# VL53L1X-TOF-Sensor.net
KiCad netlist of a schematic drawn in EAGLE
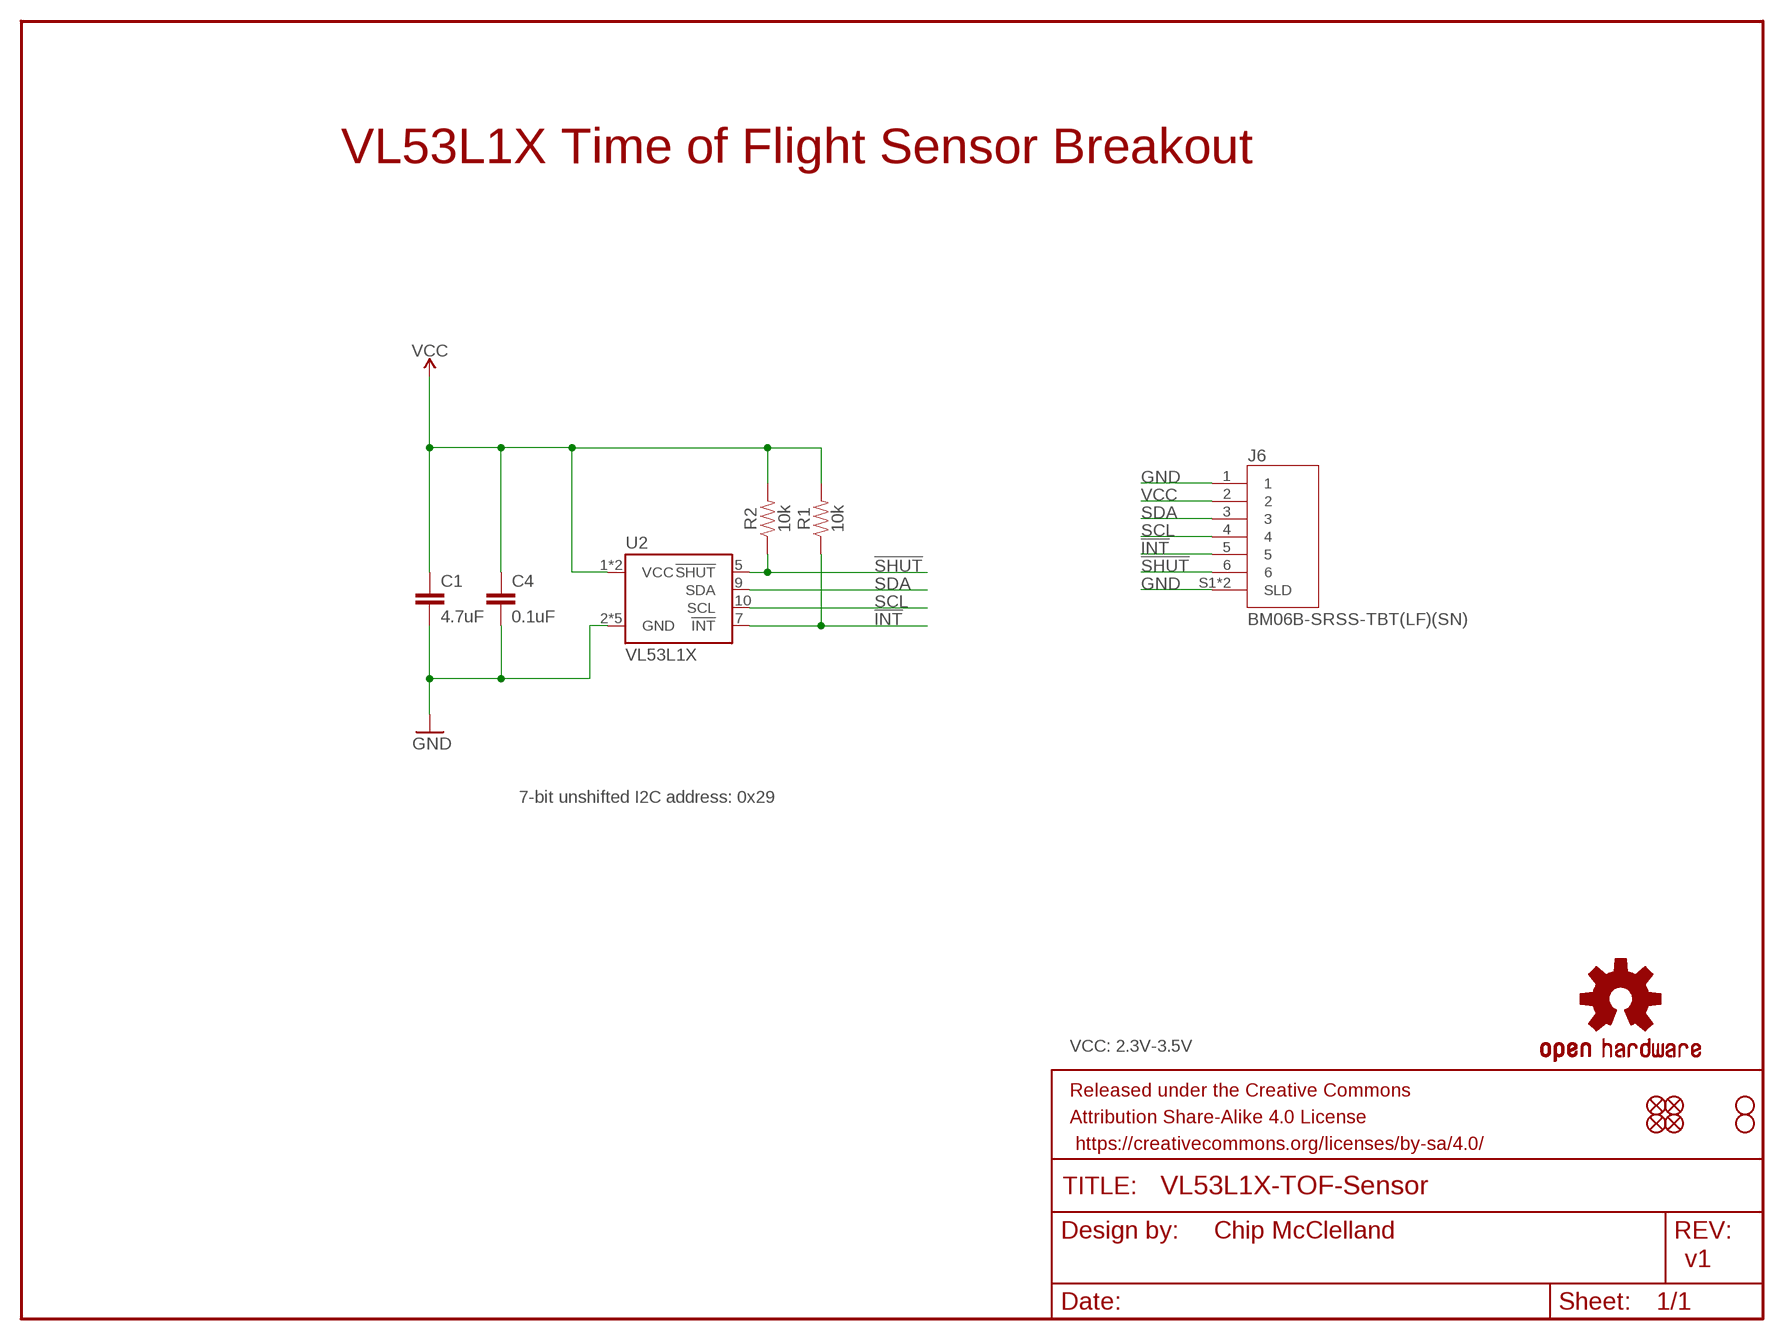
[diagram p0: schematic, sheet 1]

(export (version "E")
  (design (tool "Eeschema 10.0.6"))
  (components
    (comp (ref "C1")
      (value "4.7uF")
      (footprint "eagle-import:0603")
      (libsource (lib "eagle-import") (part "4.7UF0603"))
    )
    (comp (ref "C4")
      (value "0.1uF")
      (footprint "eagle-import:0603")
      (libsource (lib "eagle-import") (part "0.1UF-0603-25V-(+80/-20%)"))
    )
    (comp (ref "FRAME1")
      (value "FRAME-LETTER")
      (footprint "eagle-import:CREATIVE_COMMONS")
      (libsource (lib "eagle-import") (part "FRAME-LETTER"))
    )
    (comp (ref "J6")
      (value "BM06B-SRSS-TBT(LF)(SN)")
      (footprint "eagle-import:JST_BM06B-SRSS-TB(LF)(SN)")
      (libsource (lib "eagle-import") (part "BM06B-SRSS-TBT(LF)(SN)"))
    )
    (comp (ref "JP1")
      (value "FIDUCIALUFIDUCIAL")
      (footprint "eagle-import:MICRO-FIDUCIAL")
      (libsource (lib "eagle-import") (part "FIDUCIALUFIDUCIAL"))
    )
    (comp (ref "JP2")
      (value "FIDUCIALUFIDUCIAL")
      (footprint "eagle-import:MICRO-FIDUCIAL")
      (libsource (lib "eagle-import") (part "FIDUCIALUFIDUCIAL"))
    )
    (comp (ref "JP3")
      (value "STAND-OFF")
      (footprint "eagle-import:STAND-OFF")
      (libsource (lib "eagle-import") (part "STAND-OFF"))
    )
    (comp (ref "JP4")
      (value "STAND-OFF")
      (footprint "eagle-import:STAND-OFF")
      (libsource (lib "eagle-import") (part "STAND-OFF"))
    )
    (comp (ref "JP5")
      (value "FIDUCIALUFIDUCIAL")
      (footprint "eagle-import:MICRO-FIDUCIAL")
      (libsource (lib "eagle-import") (part "FIDUCIALUFIDUCIAL"))
    )
    (comp (ref "JP6")
      (value "FIDUCIALUFIDUCIAL")
      (footprint "eagle-import:MICRO-FIDUCIAL")
      (libsource (lib "eagle-import") (part "FIDUCIALUFIDUCIAL"))
    )
    (comp (ref "LOGO1")
      (value "OSHW-LOGOMINI")
      (footprint "eagle-import:OSHW-LOGO-MINI")
      (libsource (lib "eagle-import") (part "OSHW-LOGOMINI"))
    )
    (comp (ref "R1")
      (value "10k")
      (footprint "eagle-import:0603")
      (libsource (lib "eagle-import") (part "10KOHM-0603-1/10W-1%"))
    )
    (comp (ref "R2")
      (value "10k")
      (footprint "eagle-import:0603")
      (libsource (lib "eagle-import") (part "10KOHM-0603-1/10W-1%"))
    )
    (comp (ref "U2")
      (value "VL53L1X")
      (footprint "eagle-import:VL53L1X")
      (libsource (lib "eagle-import") (part "VL53L1XSMD"))
    )
  )
  (nets
    (net (code "1") (name "/SCL") (class "Default")
      (node (ref "J6") (pin "4") (pinfunction "4_4") (pintype "passive"))
      (node (ref "U2") (pin "10") (pinfunction "SCL_10") (pintype "bidirectional"))
    )
    (net (code "2") (name "/SDA") (class "Default")
      (node (ref "J6") (pin "3") (pinfunction "3_3") (pintype "passive"))
      (node (ref "U2") (pin "9") (pinfunction "SDA_9") (pintype "bidirectional"))
    )
    (net (code "3") (name "/~{INT}") (class "Default")
      (node (ref "J6") (pin "5") (pinfunction "5_5") (pintype "passive"))
      (node (ref "R1") (pin "1") (pinfunction "1_1") (pintype "passive"))
      (node (ref "U2") (pin "7") (pinfunction "~{INT}_7") (pintype "bidirectional"))
    )
    (net (code "4") (name "/~{SHUT}") (class "Default")
      (node (ref "J6") (pin "6") (pinfunction "6_6") (pintype "passive"))
      (node (ref "R2") (pin "1") (pinfunction "1_1") (pintype "passive"))
      (node (ref "U2") (pin "5") (pinfunction "~{SHUT}_5") (pintype "bidirectional"))
    )
    (net (code "5") (name "GND") (class "Default")
      (node (ref "C1") (pin "2") (pinfunction "2_2") (pintype "passive"))
      (node (ref "C4") (pin "2") (pinfunction "2_2") (pintype "passive"))
      (node (ref "J6") (pin "1") (pinfunction "1_1") (pintype "passive"))
      (node (ref "J6") (pin "S1") (pinfunction "SLD_S1") (pintype "passive"))
      (node (ref "J6") (pin "S2") (pinfunction "SLD_S2") (pintype "passive"))
      (node (ref "U2") (pin "12") (pinfunction "GND_12") (pintype "bidirectional"))
      (node (ref "U2") (pin "2") (pinfunction "GND_2") (pintype "bidirectional"))
      (node (ref "U2") (pin "3") (pinfunction "GND_3") (pintype "bidirectional"))
      (node (ref "U2") (pin "4") (pinfunction "GND_4") (pintype "bidirectional"))
      (node (ref "U2") (pin "6") (pinfunction "GND_6") (pintype "bidirectional"))
    )
    (net (code "6") (name "VCC") (class "Default")
      (node (ref "C1") (pin "1") (pinfunction "1_1") (pintype "passive"))
      (node (ref "C4") (pin "1") (pinfunction "1_1") (pintype "passive"))
      (node (ref "J6") (pin "2") (pinfunction "2_2") (pintype "passive"))
      (node (ref "R1") (pin "2") (pinfunction "2_2") (pintype "passive"))
      (node (ref "R2") (pin "2") (pinfunction "2_2") (pintype "passive"))
      (node (ref "U2") (pin "1") (pinfunction "VCC_1") (pintype "bidirectional"))
      (node (ref "U2") (pin "11") (pinfunction "VCC_11") (pintype "bidirectional"))
    )
  )
)
